# v5_2.net
KiCad netlist of a schematic drawn in EAGLE
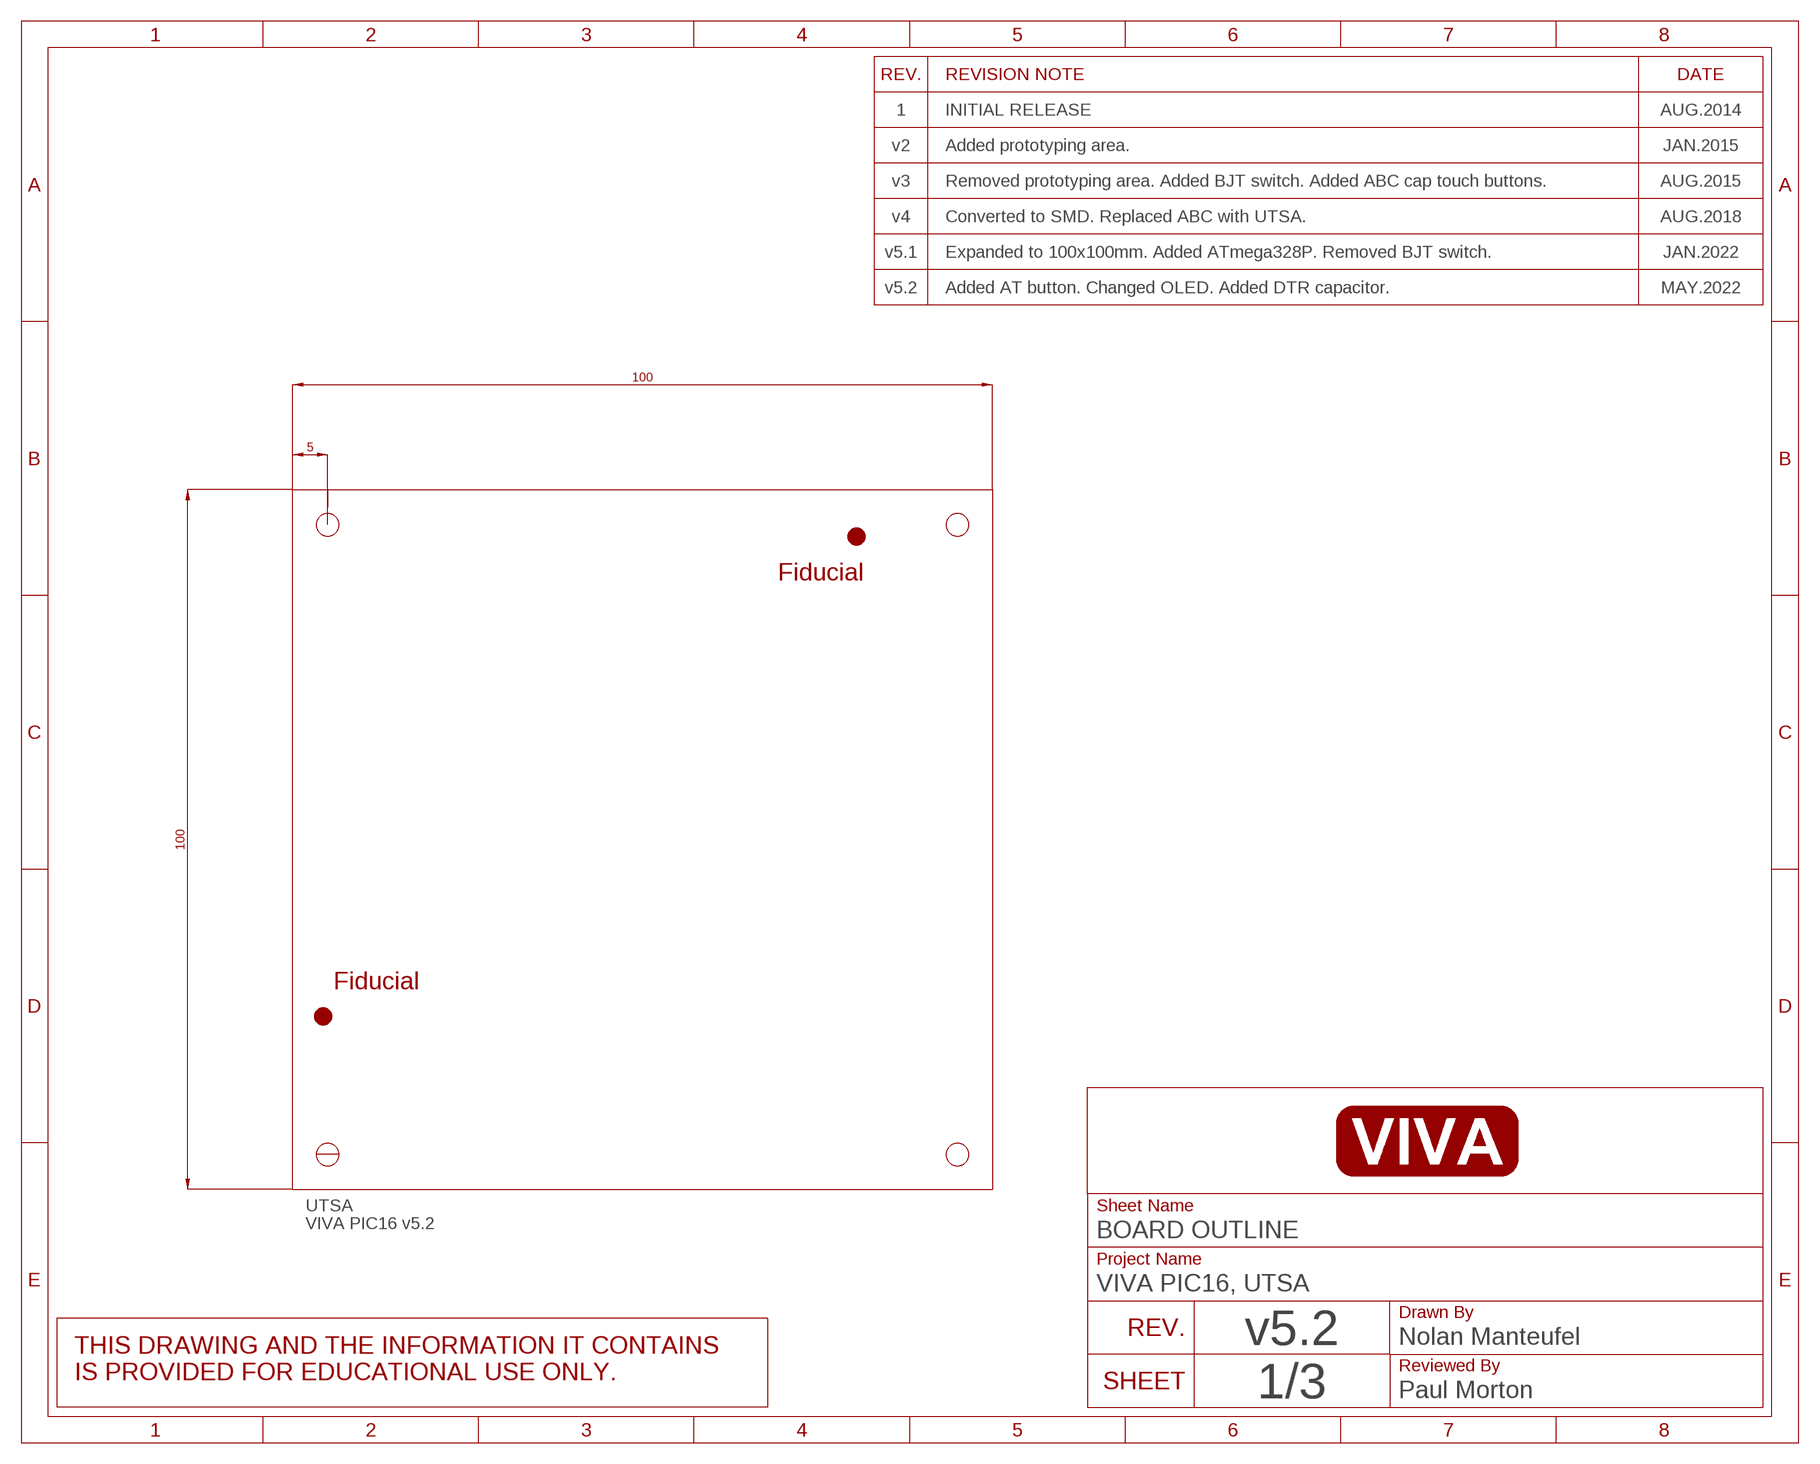
[diagram p0: schematic, sheet 1]
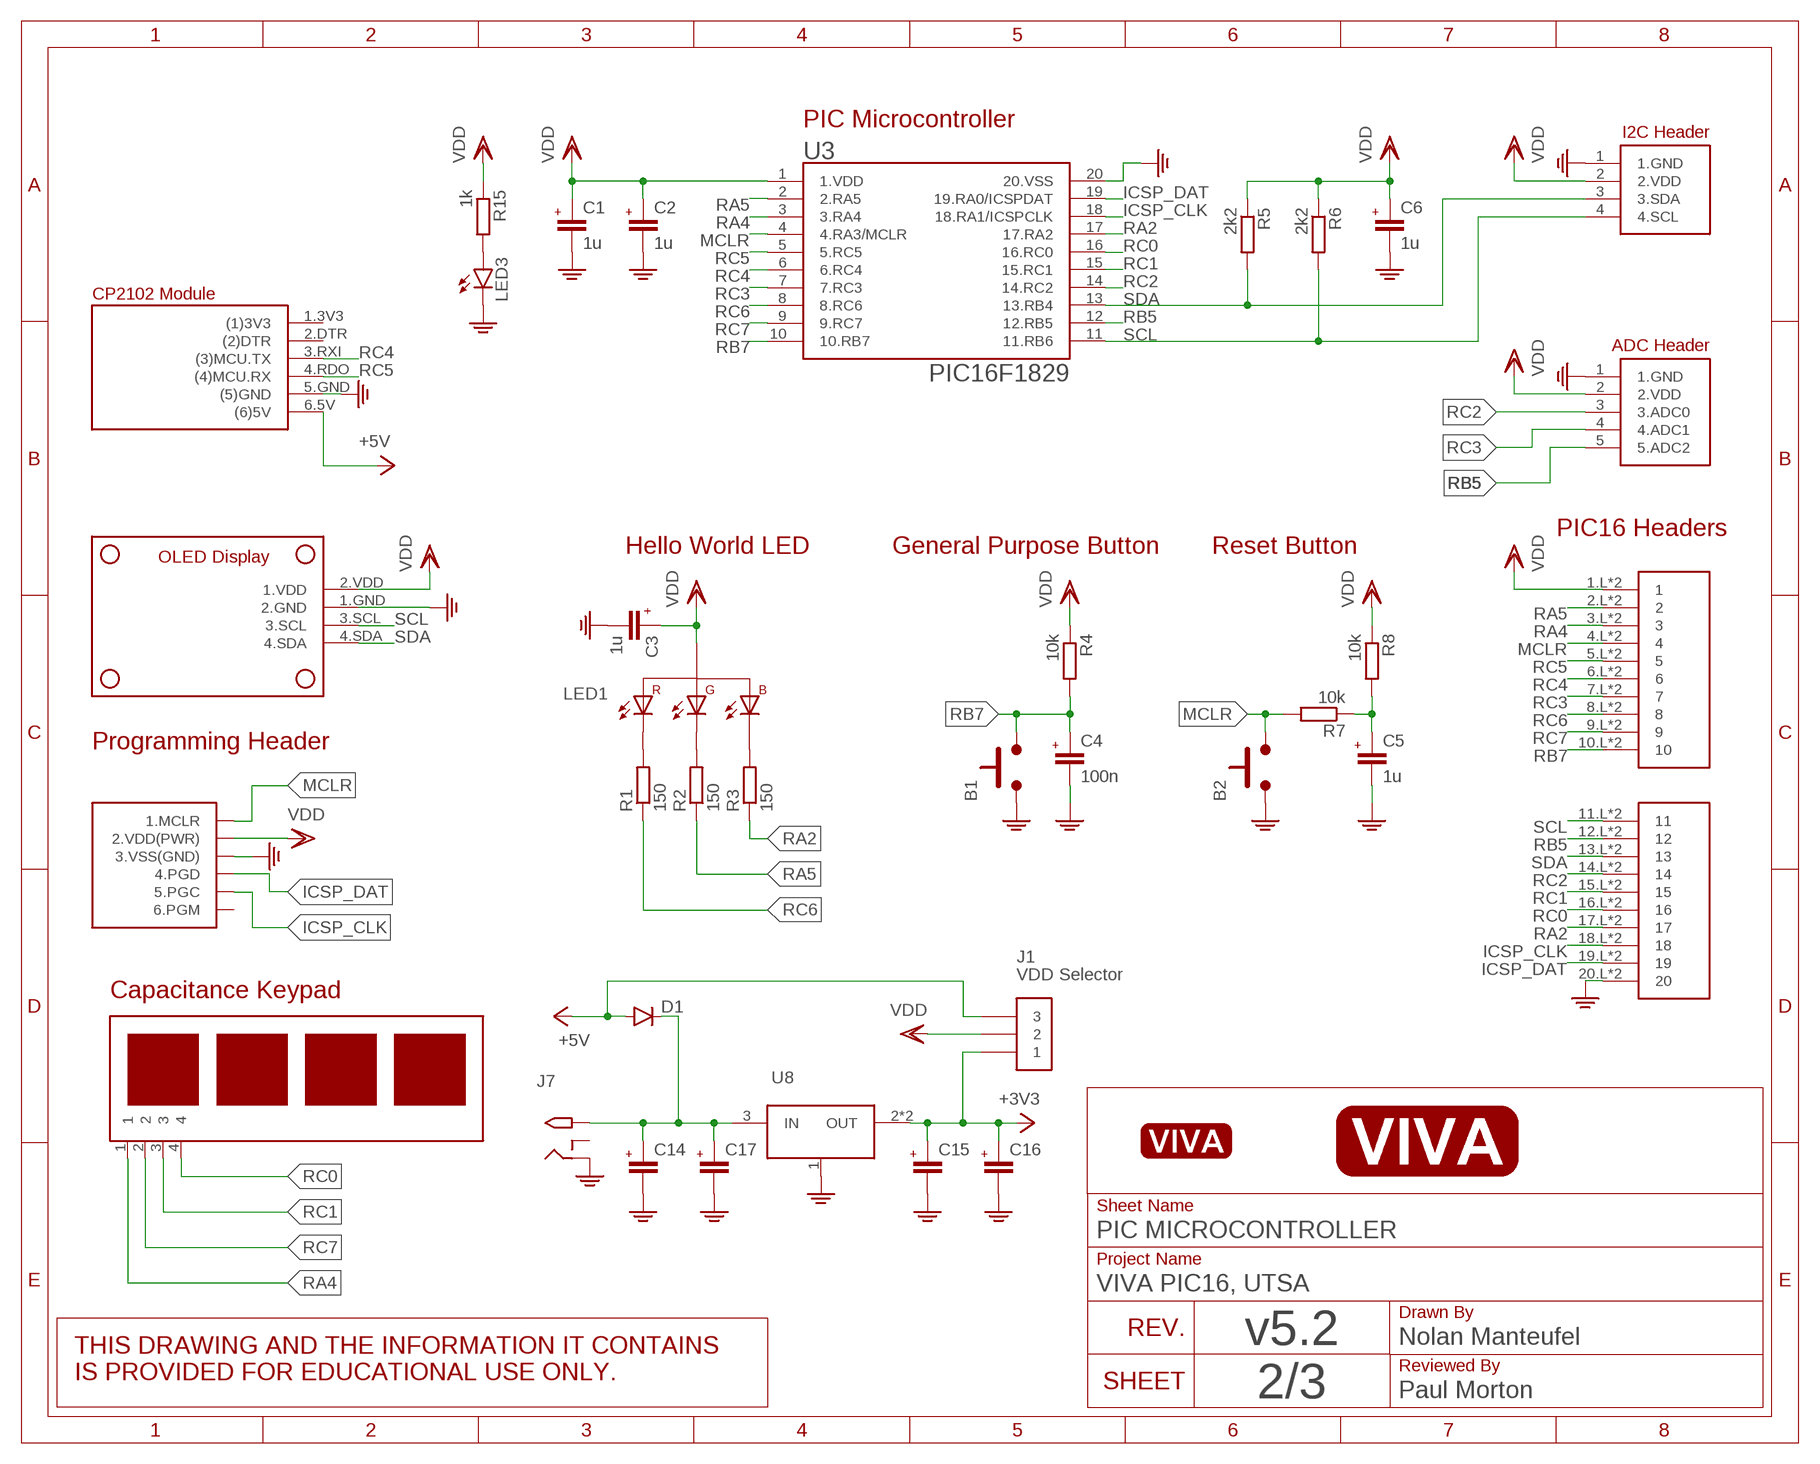
[diagram p1: schematic, sheet 2]
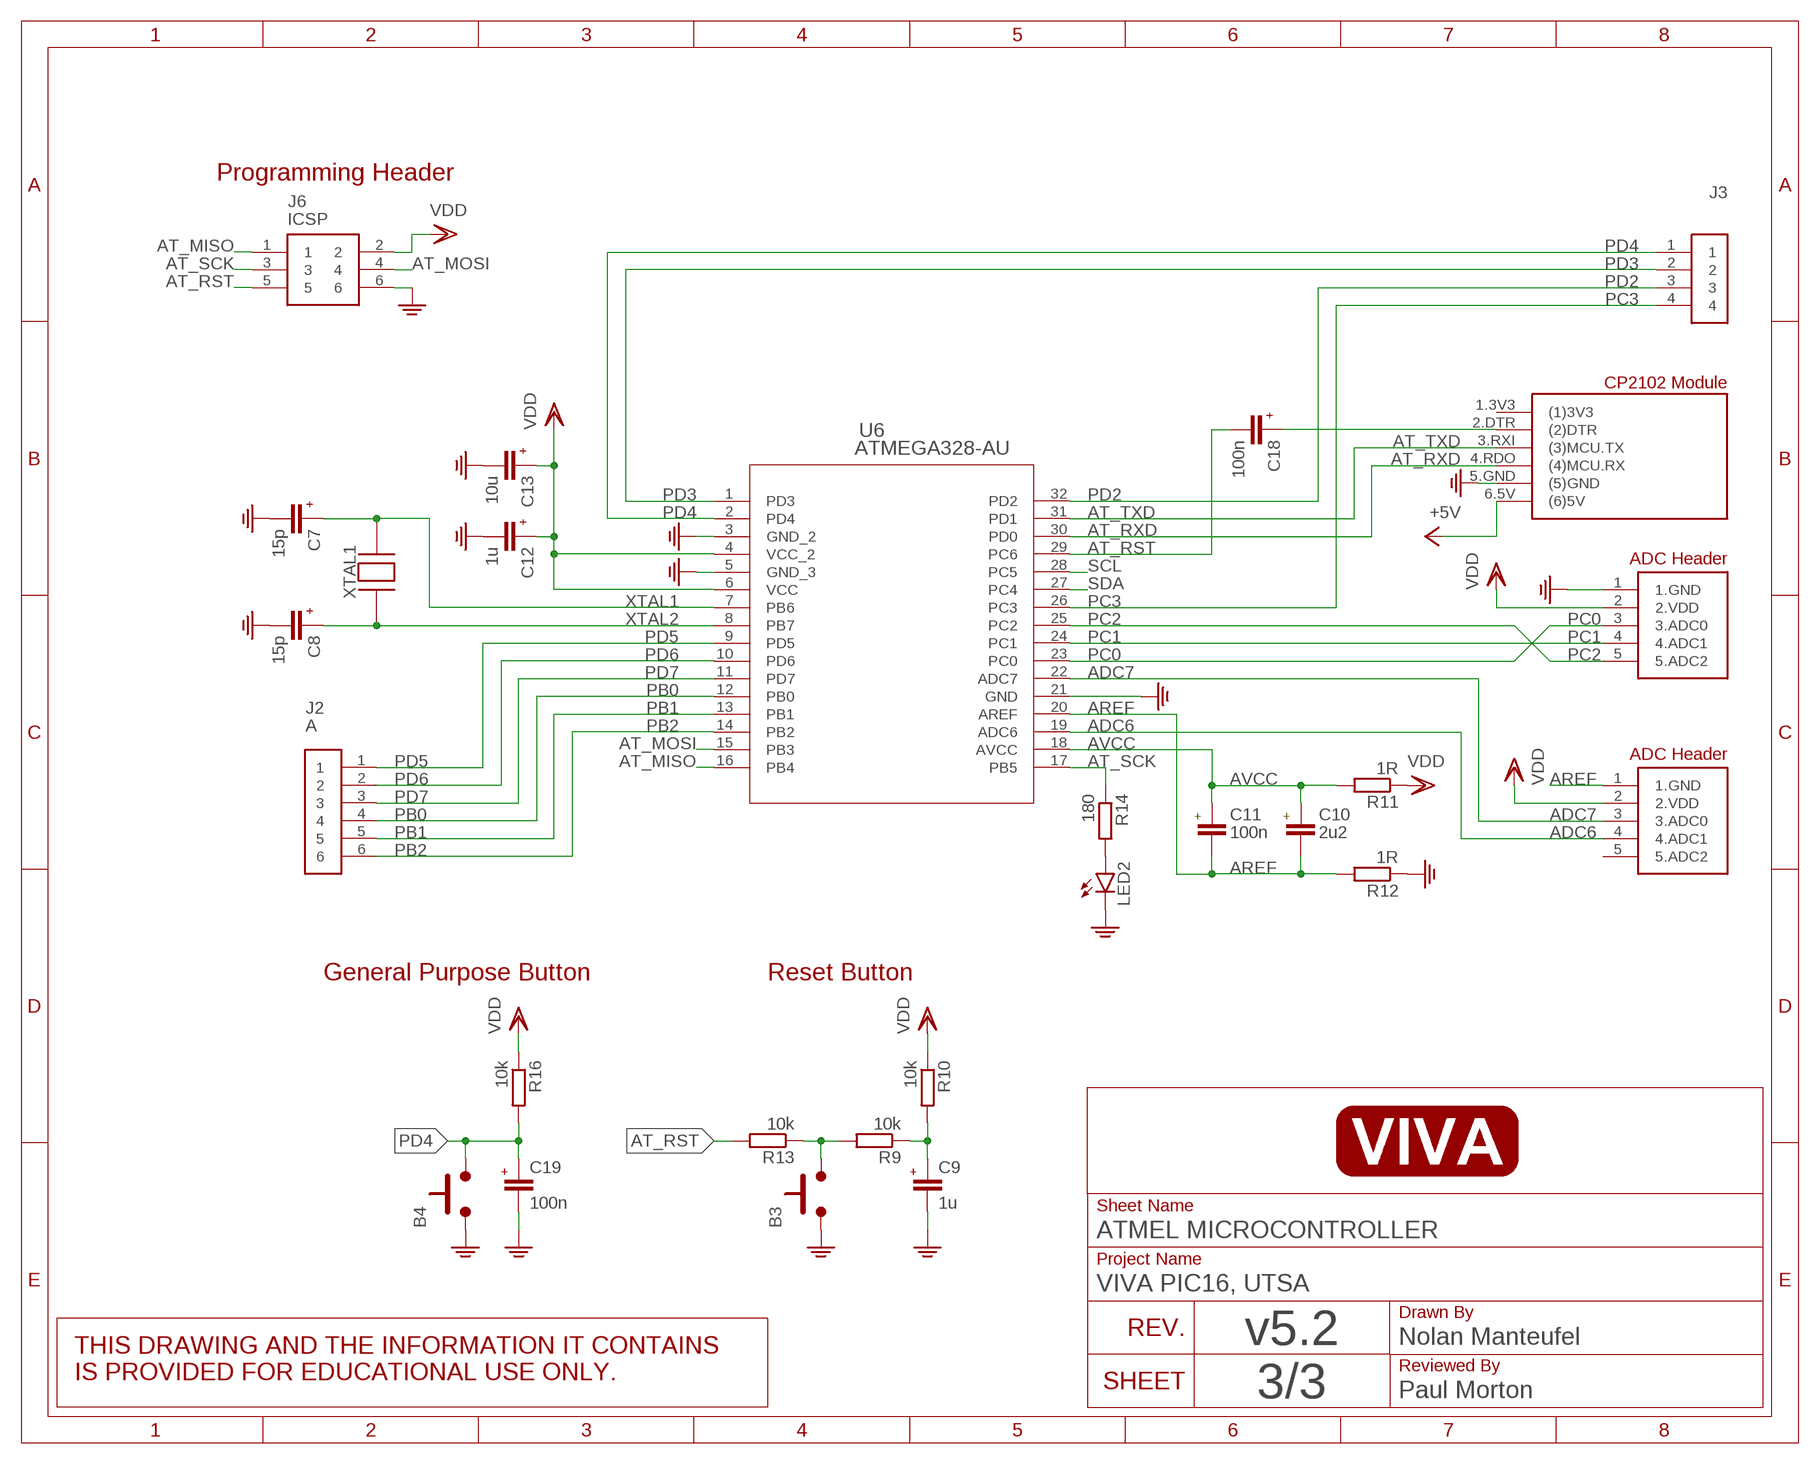
[diagram p2: schematic, sheet 3]

(export (version "E")
  (design (tool "Eeschema 10.0.6"))
  (components
    (comp (ref "A1")
      (value "FIDUCIAL")
      (footprint "eagle-import:FIDUCIAL")
      (libsource (lib "eagle-import") (part "FIDUCIAL"))
    )
    (comp (ref "A2")
      (value "FIDUCIAL")
      (footprint "eagle-import:FIDUCIAL")
      (libsource (lib "eagle-import") (part "FIDUCIAL"))
    )
    (comp (ref "UTSA")
      (value "VIVA PIC16 v5.2")
      (footprint "eagle-import:PCB_100X100")
      (libsource (lib "eagle-import") (part "PCB_100X100"))
    )
    (comp (ref "B3")
      (value "PUSHBUTTON6X6MM")
      (footprint "eagle-import:6X6MM")
      (libsource (lib "eagle-import") (part "PUSHBUTTON6X6MM"))
    )
    (comp (ref "B4")
      (value "PUSHBUTTON6X6MM")
      (footprint "eagle-import:6X6MM")
      (libsource (lib "eagle-import") (part "PUSHBUTTON6X6MM"))
    )
    (comp (ref "C7")
      (value "15p")
      (footprint "eagle-import:C0603")
      (libsource (lib "eagle-import") (part "C0603"))
    )
    (comp (ref "C8")
      (value "15p")
      (footprint "eagle-import:C0603")
      (libsource (lib "eagle-import") (part "C0603"))
    )
    (comp (ref "C9")
      (value "1u")
      (footprint "eagle-import:C0805")
      (libsource (lib "eagle-import") (part "C0805"))
    )
    (comp (ref "C10")
      (value "2u2")
      (footprint "eagle-import:C0805")
      (libsource (lib "eagle-import") (part "C-EU_C0805"))
    )
    (comp (ref "C11")
      (value "100n")
      (footprint "eagle-import:C0805")
      (libsource (lib "eagle-import") (part "C-EU_C0805"))
    )
    (comp (ref "C12")
      (value "1u")
      (footprint "eagle-import:C0805")
      (libsource (lib "eagle-import") (part "C0805"))
    )
    (comp (ref "C13")
      (value "10u")
      (footprint "eagle-import:C0805")
      (libsource (lib "eagle-import") (part "C0805"))
    )
    (comp (ref "C18")
      (value "100n")
      (footprint "eagle-import:C0805")
      (libsource (lib "eagle-import") (part "C0805"))
    )
    (comp (ref "C19")
      (value "100n")
      (footprint "eagle-import:C0805")
      (libsource (lib "eagle-import") (part "C0805"))
    )
    (comp (ref "J2")
      (value "A")
      (footprint "eagle-import:PINS_6")
      (libsource (lib "eagle-import") (part "PINS_6SQUARE"))
    )
    (comp (ref "J3")
      (value "PINS_4_0100")
      (footprint "eagle-import:PINS_4")
      (libsource (lib "eagle-import") (part "PINS_4_0100"))
    )
    (comp (ref "J6")
      (value "ICSP")
      (footprint "eagle-import:PINS_6-2X3")
      (libsource (lib "eagle-import") (part "PINS_6-2X3"))
    )
    (comp (ref "J8")
      (value "VIVA-HEADER-ADC-TEXT")
      (footprint "eagle-import:VIVA-HEADER-ADC")
      (libsource (lib "eagle-import") (part "VIVA-HEADER-ADC-TEXT"))
    )
    (comp (ref "J9")
      (value "VIVA-HEADER-ADC-TEXT")
      (footprint "eagle-import:VIVA-HEADER-ADC")
      (libsource (lib "eagle-import") (part "VIVA-HEADER-ADC-TEXT"))
    )
    (comp (ref "LED2")
      (value "LEDSML0805")
      (footprint "eagle-import:SML0805")
      (libsource (lib "eagle-import") (part "LEDSML0805"))
    )
    (comp (ref "R9")
      (value "10k")
      (footprint "eagle-import:R0805")
      (libsource (lib "eagle-import") (part "R-EU__R0805"))
    )
    (comp (ref "R10")
      (value "10k")
      (footprint "eagle-import:R0805")
      (libsource (lib "eagle-import") (part "R-EU__R0805"))
    )
    (comp (ref "R11")
      (value "1R")
      (footprint "eagle-import:R0805")
      (libsource (lib "eagle-import") (part "R-EU__R0805"))
    )
    (comp (ref "R12")
      (value "1R")
      (footprint "eagle-import:R0805")
      (libsource (lib "eagle-import") (part "R-EU__R0805"))
    )
    (comp (ref "R13")
      (value "10k")
      (footprint "eagle-import:R0805")
      (libsource (lib "eagle-import") (part "R-EU__R0805"))
    )
    (comp (ref "R14")
      (value "180")
      (footprint "eagle-import:R0805")
      (libsource (lib "eagle-import") (part "R-EU__R0805"))
    )
    (comp (ref "R16")
      (value "10k")
      (footprint "eagle-import:R0805")
      (libsource (lib "eagle-import") (part "R-EU__R0805"))
    )
    (comp (ref "U6")
      (value "ATMEGA328-AU")
      (footprint "eagle-import:32A_ATM")
      (fields (field (name "COPYRIGHT") "Copyright (C) 2021 Ultra Librarian. All rights reserved."))
      (libsource (lib "eagle-import") (part "ATMEGA328-AU"))
    )
    (comp (ref "U7")
      (value "VIVA_USB-TTL")
      (footprint "eagle-import:VIVA_USB_TTL_SUBTEXT")
      (libsource (lib "eagle-import") (part "VIVA_USB-TTL"))
    )
    (comp (ref "XTAL1")
      (value "CRYSTAL-SMD")
      (footprint "eagle-import:HC49S-SMD")
      (libsource (lib "eagle-import") (part "CRYSTAL-SMD"))
    )
    (comp (ref "B1")
      (value "PUSHBUTTON6X6MM")
      (footprint "eagle-import:6X6MM")
      (libsource (lib "eagle-import") (part "PUSHBUTTON6X6MM"))
    )
    (comp (ref "B2")
      (value "PUSHBUTTON6X6MM")
      (footprint "eagle-import:6X6MM")
      (libsource (lib "eagle-import") (part "PUSHBUTTON6X6MM"))
    )
    (comp (ref "C1")
      (value "1u")
      (footprint "eagle-import:C0805")
      (libsource (lib "eagle-import") (part "C0805"))
    )
    (comp (ref "C2")
      (value "1u")
      (footprint "eagle-import:C0805")
      (libsource (lib "eagle-import") (part "C0805"))
    )
    (comp (ref "C3")
      (value "1u")
      (footprint "eagle-import:C0805")
      (libsource (lib "eagle-import") (part "C0805"))
    )
    (comp (ref "C4")
      (value "100n")
      (footprint "eagle-import:C0805")
      (libsource (lib "eagle-import") (part "C0805"))
    )
    (comp (ref "C5")
      (value "1u")
      (footprint "eagle-import:C0805")
      (libsource (lib "eagle-import") (part "C0805"))
    )
    (comp (ref "C6")
      (value "1u")
      (footprint "eagle-import:C0805")
      (libsource (lib "eagle-import") (part "C0805"))
    )
    (comp (ref "C14")
      (value "C0805")
      (footprint "eagle-import:C0805")
      (libsource (lib "eagle-import") (part "C0805"))
    )
    (comp (ref "C15")
      (value "C0805")
      (footprint "eagle-import:C0805")
      (libsource (lib "eagle-import") (part "C0805"))
    )
    (comp (ref "C16")
      (value "C0805")
      (footprint "eagle-import:C0805")
      (libsource (lib "eagle-import") (part "C0805"))
    )
    (comp (ref "C17")
      (value "C0805")
      (footprint "eagle-import:C0805")
      (libsource (lib "eagle-import") (part "C0805"))
    )
    (comp (ref "D1")
      (value "DIODE-DO214AC")
      (footprint "eagle-import:DO214AC")
      (libsource (lib "eagle-import") (part "DIODE-DO214AC"))
    )
    (comp (ref "J1")
      (value "VDD Selector")
      (footprint "eagle-import:PINS_3")
      (libsource (lib "eagle-import") (part "PINS_3_2.54"))
    )
    (comp (ref "J4")
      (value "PICKIT3")
      (footprint "eagle-import:PICKIT3")
      (libsource (lib "eagle-import") (part "PICKIT3"))
    )
    (comp (ref "J5")
      (value "VIVA-HEADER-ADC-PIC16")
      (footprint "eagle-import:VIVA-HEADER-ADC-PIC16")
      (libsource (lib "eagle-import") (part "VIVA-HEADER-ADC-PIC16"))
    )
    (comp (ref "J7")
      (value "2.1MMJACKTHM")
      (footprint "eagle-import:PJ-102A")
      (libsource (lib "eagle-import") (part "2.1MMJACKTHM"))
    )
    (comp (ref "LED1")
      (value "LED_RGBLTST-C19FD1WT")
      (footprint "eagle-import:0805_RGB")
      (libsource (lib "eagle-import") (part "LED_RGBLTST-C19FD1WT"))
    )
    (comp (ref "LED3")
      (value "LEDSML0805")
      (footprint "eagle-import:SML0805")
      (libsource (lib "eagle-import") (part "LEDSML0805"))
    )
    (comp (ref "R1")
      (value "150")
      (footprint "eagle-import:R0805")
      (libsource (lib "eagle-import") (part "R-EU__R0805"))
    )
    (comp (ref "R2")
      (value "150")
      (footprint "eagle-import:R0805")
      (libsource (lib "eagle-import") (part "R-EU__R0805"))
    )
    (comp (ref "R3")
      (value "150")
      (footprint "eagle-import:R0805")
      (libsource (lib "eagle-import") (part "R-EU__R0805"))
    )
    (comp (ref "R4")
      (value "10k")
      (footprint "eagle-import:R0805")
      (libsource (lib "eagle-import") (part "R-EU__R0805"))
    )
    (comp (ref "R5")
      (value "2k2")
      (footprint "eagle-import:R0805")
      (libsource (lib "eagle-import") (part "R-EU__R0805"))
    )
    (comp (ref "R6")
      (value "2k2")
      (footprint "eagle-import:R0805")
      (libsource (lib "eagle-import") (part "R-EU__R0805"))
    )
    (comp (ref "R7")
      (value "10k")
      (footprint "eagle-import:R0805")
      (libsource (lib "eagle-import") (part "R-EU__R0805"))
    )
    (comp (ref "R8")
      (value "10k")
      (footprint "eagle-import:R0805")
      (libsource (lib "eagle-import") (part "R-EU__R0805"))
    )
    (comp (ref "R15")
      (value "1k")
      (footprint "eagle-import:R0805")
      (libsource (lib "eagle-import") (part "R-EU__R0805"))
    )
    (comp (ref "U$2")
      (value "VIVA_LOGO")
      (footprint "eagle-import:VIVA_LOGO")
      (libsource (lib "eagle-import") (part "VIVA_LOGO"))
    )
    (comp (ref "U$3")
      (value "VIVA_OLEDGND")
      (footprint "eagle-import:VIVA_OLED-I2C-ALT")
      (libsource (lib "eagle-import") (part "VIVA_OLEDGND"))
    )
    (comp (ref "U1")
      (value "VIVA_UTSA-KEYPADV5")
      (footprint "eagle-import:VIVA_UTSA-KEYPAD-V5")
      (libsource (lib "eagle-import") (part "VIVA_UTSA-KEYPADV5"))
    )
    (comp (ref "U2")
      (value "VIVA_USB-TTL")
      (footprint "eagle-import:VIVA_USB_TTL_SUBTEXT")
      (libsource (lib "eagle-import") (part "VIVA_USB-TTL"))
    )
    (comp (ref "U3")
      (value "PIC16F1829")
      (footprint "eagle-import:SOP20-NEW")
      (libsource (lib "eagle-import") (part "PIC16F1829300"))
    )
    (comp (ref "U4")
      (value "VIVA-HEADER-I2C-RA")
      (footprint "eagle-import:VIVA-HEADER-I2C-RA")
      (libsource (lib "eagle-import") (part "VIVA-HEADER-I2C-RA"))
    )
    (comp (ref "U5")
      (value "VIVA_PIC16BOARD")
      (footprint "eagle-import:VIVA_PIC16")
      (libsource (lib "eagle-import") (part "VIVA_PIC16BOARD"))
    )
    (comp (ref "U8")
      (value "REGULATOR_SCHLM1117")
      (footprint "eagle-import:SOT223")
      (libsource (lib "eagle-import") (part "REGULATOR_SCHLM1117"))
    )
  )
  (nets
    (net (code "1") (name "+3V3") (class "Default")
      (node (ref "C15") (pin "1") (pinfunction "+_1") (pintype "passive"))
      (node (ref "C16") (pin "1") (pinfunction "+_1") (pintype "passive"))
      (node (ref "J1") (pin "1") (pinfunction "1_1") (pintype "bidirectional"))
      (node (ref "U8") (pin "2") (pinfunction "OUT_2") (pintype "bidirectional"))
      (node (ref "U8") (pin "4.TAB") (pinfunction "OUT_4.TAB") (pintype "bidirectional"))
    )
    (net (code "2") (name "+5V") (class "Default")
      (node (ref "D1") (pin "A") (pinfunction "A_A") (pintype "passive"))
      (node (ref "J1") (pin "3") (pinfunction "3_3") (pintype "bidirectional"))
      (node (ref "U2") (pin "6.5V") (pinfunction "(6)5V_6.5V") (pintype "bidirectional"))
      (node (ref "U7") (pin "6.5V") (pinfunction "(6)5V_6.5V") (pintype "bidirectional"))
    )
    (net (code "3") (name "ADC6") (class "Default")
      (node (ref "J8") (pin "4") (pinfunction "4.ADC1_4") (pintype "bidirectional"))
      (node (ref "U6") (pin "19") (pinfunction "ADC6_19") (pintype "passive"))
    )
    (net (code "4") (name "ADC7") (class "Default")
      (node (ref "J8") (pin "3") (pinfunction "3.ADC0_3") (pintype "bidirectional"))
      (node (ref "U6") (pin "22") (pinfunction "ADC7_22") (pintype "passive"))
    )
    (net (code "5") (name "AREF") (class "Default")
      (node (ref "C10") (pin "2") (pinfunction "2_2") (pintype "passive"))
      (node (ref "C11") (pin "2") (pinfunction "2_2") (pintype "passive"))
      (node (ref "J8") (pin "1") (pinfunction "1.GND_1") (pintype "bidirectional"))
      (node (ref "R12") (pin "2") (pinfunction "2_2") (pintype "passive"))
      (node (ref "U6") (pin "20") (pinfunction "AREF_20") (pintype "passive"))
    )
    (net (code "6") (name "AT_MISO") (class "Default")
      (node (ref "J6") (pin "1") (pinfunction "1_1") (pintype "bidirectional"))
      (node (ref "U6") (pin "16") (pinfunction "PB4_16") (pintype "bidirectional"))
    )
    (net (code "7") (name "AT_MOSI") (class "Default")
      (node (ref "J6") (pin "4") (pinfunction "4_4") (pintype "bidirectional"))
      (node (ref "U6") (pin "15") (pinfunction "PB3_15") (pintype "bidirectional"))
    )
    (net (code "8") (name "AT_RST") (class "Default")
      (node (ref "C18") (pin "2") (pinfunction "-_2") (pintype "passive"))
      (node (ref "J6") (pin "5") (pinfunction "5_5") (pintype "bidirectional"))
      (node (ref "R13") (pin "2") (pinfunction "2_2") (pintype "passive"))
      (node (ref "U6") (pin "29") (pinfunction "PC6_29") (pintype "bidirectional"))
    )
    (net (code "9") (name "AT_RXD") (class "Default")
      (node (ref "U6") (pin "30") (pinfunction "PD0_30") (pintype "bidirectional"))
      (node (ref "U7") (pin "4.RDO") (pinfunction "(4)MCU.RX_4.RDO") (pintype "bidirectional"))
    )
    (net (code "10") (name "AT_SCK") (class "Default")
      (node (ref "J6") (pin "3") (pinfunction "3_3") (pintype "bidirectional"))
      (node (ref "R14") (pin "1") (pinfunction "1_1") (pintype "passive"))
      (node (ref "U6") (pin "17") (pinfunction "PB5_17") (pintype "bidirectional"))
    )
    (net (code "11") (name "AT_TXD") (class "Default")
      (node (ref "U6") (pin "31") (pinfunction "PD1_31") (pintype "bidirectional"))
      (node (ref "U7") (pin "3.RXI") (pinfunction "(3)MCU.TX_3.RXI") (pintype "bidirectional"))
    )
    (net (code "12") (name "AVCC") (class "Default")
      (node (ref "C10") (pin "1") (pinfunction "1_1") (pintype "passive"))
      (node (ref "C11") (pin "1") (pinfunction "1_1") (pintype "passive"))
      (node (ref "R11") (pin "2") (pinfunction "2_2") (pintype "passive"))
      (node (ref "U6") (pin "18") (pinfunction "AVCC_18") (pintype "power_in"))
    )
    (net (code "13") (name "GND") (class "Default")
      (node (ref "B1") (pin "1.A") (pinfunction "1_1.A") (pintype "bidirectional"))
      (node (ref "B1") (pin "2.A") (pinfunction "1_2.A") (pintype "bidirectional"))
      (node (ref "B2") (pin "1.A") (pinfunction "1_1.A") (pintype "bidirectional"))
      (node (ref "B2") (pin "2.A") (pinfunction "1_2.A") (pintype "bidirectional"))
      (node (ref "B3") (pin "1.A") (pinfunction "1_1.A") (pintype "bidirectional"))
      (node (ref "B3") (pin "2.A") (pinfunction "1_2.A") (pintype "bidirectional"))
      (node (ref "B4") (pin "1.A") (pinfunction "1_1.A") (pintype "bidirectional"))
      (node (ref "B4") (pin "2.A") (pinfunction "1_2.A") (pintype "bidirectional"))
      (node (ref "C1") (pin "2") (pinfunction "-_2") (pintype "passive"))
      (node (ref "C12") (pin "2") (pinfunction "-_2") (pintype "passive"))
      (node (ref "C13") (pin "2") (pinfunction "-_2") (pintype "passive"))
      (node (ref "C14") (pin "2") (pinfunction "-_2") (pintype "passive"))
      (node (ref "C15") (pin "2") (pinfunction "-_2") (pintype "passive"))
      (node (ref "C16") (pin "2") (pinfunction "-_2") (pintype "passive"))
      (node (ref "C17") (pin "2") (pinfunction "-_2") (pintype "passive"))
      (node (ref "C19") (pin "2") (pinfunction "-_2") (pintype "passive"))
      (node (ref "C2") (pin "2") (pinfunction "-_2") (pintype "passive"))
      (node (ref "C3") (pin "2") (pinfunction "-_2") (pintype "passive"))
      (node (ref "C4") (pin "2") (pinfunction "-_2") (pintype "passive"))
      (node (ref "C5") (pin "2") (pinfunction "-_2") (pintype "passive"))
      (node (ref "C6") (pin "2") (pinfunction "-_2") (pintype "passive"))
      (node (ref "C7") (pin "1") (pinfunction "-_1") (pintype "passive"))
      (node (ref "C8") (pin "1") (pinfunction "-_1") (pintype "passive"))
      (node (ref "C9") (pin "2") (pinfunction "-_2") (pintype "passive"))
      (node (ref "J4") (pin "3") (pinfunction "3.VSS(GND)_3") (pintype "bidirectional"))
      (node (ref "J5") (pin "1") (pinfunction "1.GND_1") (pintype "bidirectional"))
      (node (ref "J6") (pin "6") (pinfunction "6_6") (pintype "bidirectional"))
      (node (ref "J7") (pin "RING") (pinfunction "RING_RING") (pintype "bidirectional"))
      (node (ref "J9") (pin "1") (pinfunction "1.GND_1") (pintype "bidirectional"))
      (node (ref "LED2") (pin "C") (pinfunction "C_C") (pintype "passive"))
      (node (ref "LED3") (pin "C") (pinfunction "C_C") (pintype "passive"))
      (node (ref "R12") (pin "1") (pinfunction "1_1") (pintype "passive"))
      (node (ref "U$3") (pin "1.GND") (pinfunction "2.GND_1.GND") (pintype "bidirectional"))
      (node (ref "U2") (pin "5.GND") (pinfunction "(5)GND_5.GND") (pintype "bidirectional"))
      (node (ref "U3") (pin "20") (pinfunction "20.VSS_20") (pintype "bidirectional"))
      (node (ref "U4") (pin "1") (pinfunction "1.GND_1") (pintype "bidirectional"))
      (node (ref "U5") (pin "20.L") (pinfunction "20_20.L") (pintype "bidirectional"))
      (node (ref "U5") (pin "20.R") (pinfunction "20_20.R") (pintype "bidirectional"))
      (node (ref "U6") (pin "21") (pinfunction "GND_21") (pintype "power_in"))
      (node (ref "U6") (pin "3") (pinfunction "GND_2_3") (pintype "power_in"))
      (node (ref "U6") (pin "5") (pinfunction "GND_3_5") (pintype "power_in"))
      (node (ref "U7") (pin "5.GND") (pinfunction "(5)GND_5.GND") (pintype "bidirectional"))
      (node (ref "U8") (pin "1") (pinfunction "GND_1") (pintype "bidirectional"))
    )
    (net (code "14") (name "ICSP_CLK") (class "Default")
      (node (ref "J4") (pin "5") (pinfunction "5.PGC_5") (pintype "bidirectional"))
      (node (ref "U3") (pin "18") (pinfunction "18.RA1/ICSPCLK_18") (pintype "bidirectional"))
      (node (ref "U5") (pin "18.L") (pinfunction "18_18.L") (pintype "bidirectional"))
      (node (ref "U5") (pin "18.R") (pinfunction "18_18.R") (pintype "bidirectional"))
    )
    (net (code "15") (name "ICSP_DAT") (class "Default")
      (node (ref "J4") (pin "4") (pinfunction "4.PGD_4") (pintype "bidirectional"))
      (node (ref "U3") (pin "19") (pinfunction "19.RA0/ICSPDAT_19") (pintype "bidirectional"))
      (node (ref "U5") (pin "19.L") (pinfunction "19_19.L") (pintype "bidirectional"))
      (node (ref "U5") (pin "19.R") (pinfunction "19_19.R") (pintype "bidirectional"))
    )
    (net (code "16") (name "MCLR") (class "Default")
      (node (ref "B2") (pin "3.B") (pinfunction "2_3.B") (pintype "bidirectional"))
      (node (ref "B2") (pin "4.B") (pinfunction "2_4.B") (pintype "bidirectional"))
      (node (ref "J4") (pin "1") (pinfunction "1.MCLR_1") (pintype "bidirectional"))
      (node (ref "R7") (pin "2") (pinfunction "2_2") (pintype "passive"))
      (node (ref "U3") (pin "4") (pinfunction "4.RA3/MCLR_4") (pintype "bidirectional"))
      (node (ref "U5") (pin "4.L") (pinfunction "4_4.L") (pintype "bidirectional"))
      (node (ref "U5") (pin "4.R") (pinfunction "4_4.R") (pintype "bidirectional"))
    )
    (net (code "17") (name "Net-(B3-2-Pad3.B)") (class "Default")
      (node (ref "B3") (pin "3.B") (pinfunction "2_3.B") (pintype "bidirectional"))
      (node (ref "B3") (pin "4.B") (pinfunction "2_4.B") (pintype "bidirectional"))
      (node (ref "R13") (pin "1") (pinfunction "1_1") (pintype "passive"))
      (node (ref "R9") (pin "2") (pinfunction "2_2") (pintype "passive"))
    )
    (net (code "18") (name "Net-(C5-+)") (class "Default")
      (node (ref "C5") (pin "1") (pinfunction "+_1") (pintype "passive"))
      (node (ref "R7") (pin "1") (pinfunction "1_1") (pintype "passive"))
      (node (ref "R8") (pin "2") (pinfunction "2_2") (pintype "passive"))
    )
    (net (code "19") (name "Net-(C9-+)") (class "Default")
      (node (ref "C9") (pin "1") (pinfunction "+_1") (pintype "passive"))
      (node (ref "R10") (pin "2") (pinfunction "2_2") (pintype "passive"))
      (node (ref "R9") (pin "1") (pinfunction "1_1") (pintype "passive"))
    )
    (net (code "20") (name "Net-(C14-+)") (class "Default")
      (node (ref "C14") (pin "1") (pinfunction "+_1") (pintype "passive"))
      (node (ref "C17") (pin "1") (pinfunction "+_1") (pintype "passive"))
      (node (ref "D1") (pin "C") (pinfunction "C_C") (pintype "passive"))
      (node (ref "J7") (pin "TIP") (pinfunction "TIP_TIP") (pintype "bidirectional"))
      (node (ref "U8") (pin "3") (pinfunction "IN_3") (pintype "bidirectional"))
    )
    (net (code "21") (name "Net-(C18-+)") (class "Default")
      (node (ref "C18") (pin "1") (pinfunction "+_1") (pintype "passive"))
      (node (ref "U7") (pin "2.DTR") (pinfunction "(2)DTR_2.DTR") (pintype "bidirectional"))
    )
    (net (code "22") (name "Net-(LED1-1.R-)") (class "Default")
      (node (ref "LED1") (pin "2") (pinfunction "1.R-_2") (pintype "passive"))
      (node (ref "R1") (pin "2") (pinfunction "2_2") (pintype "passive"))
    )
    (net (code "23") (name "Net-(LED1-2.G-)") (class "Default")
      (node (ref "LED1") (pin "3") (pinfunction "2.G-_3") (pintype "passive"))
      (node (ref "R2") (pin "2") (pinfunction "2_2") (pintype "passive"))
    )
    (net (code "24") (name "Net-(LED1-4.B-)") (class "Default")
      (node (ref "LED1") (pin "1") (pinfunction "4.B-_1") (pintype "passive"))
      (node (ref "R3") (pin "2") (pinfunction "2_2") (pintype "passive"))
    )
    (net (code "25") (name "Net-(LED2-PadA)") (class "Default")
      (node (ref "LED2") (pin "A") (pinfunction "A_A") (pintype "passive"))
      (node (ref "R14") (pin "2") (pinfunction "2_2") (pintype "passive"))
    )
    (net (code "26") (name "Net-(LED3-PadA)") (class "Default")
      (node (ref "LED3") (pin "A") (pinfunction "A_A") (pintype "passive"))
      (node (ref "R15") (pin "2") (pinfunction "2_2") (pintype "passive"))
    )
    (net (code "27") (name "PB0") (class "Default")
      (node (ref "J2") (pin "4") (pinfunction "4_4") (pintype "bidirectional"))
      (node (ref "U6") (pin "12") (pinfunction "PB0_12") (pintype "bidirectional"))
    )
    (net (code "28") (name "PB1") (class "Default")
      (node (ref "J2") (pin "5") (pinfunction "5_5") (pintype "bidirectional"))
      (node (ref "U6") (pin "13") (pinfunction "PB1_13") (pintype "bidirectional"))
    )
    (net (code "29") (name "PB2") (class "Default")
      (node (ref "J2") (pin "6") (pinfunction "6_6") (pintype "bidirectional"))
      (node (ref "U6") (pin "14") (pinfunction "PB2_14") (pintype "bidirectional"))
    )
    (net (code "30") (name "PC0") (class "Default")
      (node (ref "J9") (pin "3") (pinfunction "3.ADC0_3") (pintype "bidirectional"))
      (node (ref "U6") (pin "23") (pinfunction "PC0_23") (pintype "bidirectional"))
    )
    (net (code "31") (name "PC1") (class "Default")
      (node (ref "J9") (pin "4") (pinfunction "4.ADC1_4") (pintype "bidirectional"))
      (node (ref "U6") (pin "24") (pinfunction "PC1_24") (pintype "bidirectional"))
    )
    (net (code "32") (name "PC2") (class "Default")
      (node (ref "J9") (pin "5") (pinfunction "5.ADC2_5") (pintype "bidirectional"))
      (node (ref "U6") (pin "25") (pinfunction "PC2_25") (pintype "bidirectional"))
    )
    (net (code "33") (name "PC3") (class "Default")
      (node (ref "J3") (pin "4") (pinfunction "4_4") (pintype "bidirectional"))
      (node (ref "U6") (pin "26") (pinfunction "PC3_26") (pintype "bidirectional"))
    )
    (net (code "34") (name "PD2") (class "Default")
      (node (ref "J3") (pin "3") (pinfunction "3_3") (pintype "bidirectional"))
      (node (ref "U6") (pin "32") (pinfunction "PD2_32") (pintype "bidirectional"))
    )
    (net (code "35") (name "PD3") (class "Default")
      (node (ref "J3") (pin "2") (pinfunction "2_2") (pintype "bidirectional"))
      (node (ref "U6") (pin "1") (pinfunction "PD3_1") (pintype "bidirectional"))
    )
    (net (code "36") (name "PD4") (class "Default")
      (node (ref "B4") (pin "3.B") (pinfunction "2_3.B") (pintype "bidirectional"))
      (node (ref "B4") (pin "4.B") (pinfunction "2_4.B") (pintype "bidirectional"))
      (node (ref "C19") (pin "1") (pinfunction "+_1") (pintype "passive"))
      (node (ref "J3") (pin "1") (pinfunction "1_1") (pintype "bidirectional"))
      (node (ref "R16") (pin "2") (pinfunction "2_2") (pintype "passive"))
      (node (ref "U6") (pin "2") (pinfunction "PD4_2") (pintype "bidirectional"))
    )
    (net (code "37") (name "PD5") (class "Default")
      (node (ref "J2") (pin "1") (pinfunction "1_1") (pintype "bidirectional"))
      (node (ref "U6") (pin "9") (pinfunction "PD5_9") (pintype "bidirectional"))
    )
    (net (code "38") (name "PD6") (class "Default")
      (node (ref "J2") (pin "2") (pinfunction "2_2") (pintype "bidirectional"))
      (node (ref "U6") (pin "10") (pinfunction "PD6_10") (pintype "bidirectional"))
    )
    (net (code "39") (name "PD7") (class "Default")
      (node (ref "J2") (pin "3") (pinfunction "3_3") (pintype "bidirectional"))
      (node (ref "U6") (pin "11") (pinfunction "PD7_11") (pintype "bidirectional"))
    )
    (net (code "40") (name "RA2") (class "Default")
      (node (ref "R3") (pin "1") (pinfunction "1_1") (pintype "passive"))
      (node (ref "U3") (pin "17") (pinfunction "17.RA2_17") (pintype "bidirectional"))
      (node (ref "U5") (pin "17.L") (pinfunction "17_17.L") (pintype "bidirectional"))
      (node (ref "U5") (pin "17.R") (pinfunction "17_17.R") (pintype "bidirectional"))
    )
    (net (code "41") (name "RA4") (class "Default")
      (node (ref "U1") (pin "1") (pinfunction "1_1") (pintype "bidirectional"))
      (node (ref "U3") (pin "3") (pinfunction "3.RA4_3") (pintype "bidirectional"))
      (node (ref "U5") (pin "3.L") (pinfunction "3_3.L") (pintype "bidirectional"))
      (node (ref "U5") (pin "3.R") (pinfunction "3_3.R") (pintype "bidirectional"))
    )
    (net (code "42") (name "RA5") (class "Default")
      (node (ref "R2") (pin "1") (pinfunction "1_1") (pintype "passive"))
      (node (ref "U3") (pin "2") (pinfunction "2.RA5_2") (pintype "bidirectional"))
      (node (ref "U5") (pin "2.L") (pinfunction "2_2.L") (pintype "bidirectional"))
      (node (ref "U5") (pin "2.R") (pinfunction "2_2.R") (pintype "bidirectional"))
    )
    (net (code "43") (name "RB5") (class "Default")
      (node (ref "J5") (pin "5") (pinfunction "5.ADC2_5") (pintype "bidirectional"))
      (node (ref "U3") (pin "12") (pinfunction "12.RB5_12") (pintype "bidirectional"))
      (node (ref "U5") (pin "12.L") (pinfunction "12_12.L") (pintype "bidirectional"))
      (node (ref "U5") (pin "12.R") (pinfunction "12_12.R") (pintype "bidirectional"))
    )
    (net (code "44") (name "RB7") (class "Default")
      (node (ref "B1") (pin "3.B") (pinfunction "2_3.B") (pintype "bidirectional"))
      (node (ref "B1") (pin "4.B") (pinfunction "2_4.B") (pintype "bidirectional"))
      (node (ref "C4") (pin "1") (pinfunction "+_1") (pintype "passive"))
      (node (ref "R4") (pin "2") (pinfunction "2_2") (pintype "passive"))
      (node (ref "U3") (pin "10") (pinfunction "10.RB7_10") (pintype "bidirectional"))
      (node (ref "U5") (pin "10.L") (pinfunction "10_10.L") (pintype "bidirectional"))
      (node (ref "U5") (pin "10.R") (pinfunction "10_10.R") (pintype "bidirectional"))
    )
    (net (code "45") (name "RC0") (class "Default")
      (node (ref "U1") (pin "4") (pinfunction "4_4") (pintype "bidirectional"))
      (node (ref "U3") (pin "16") (pinfunction "16.RC0_16") (pintype "bidirectional"))
      (node (ref "U5") (pin "16.L") (pinfunction "16_16.L") (pintype "bidirectional"))
      (node (ref "U5") (pin "16.R") (pinfunction "16_16.R") (pintype "bidirectional"))
    )
    (net (code "46") (name "RC1") (class "Default")
      (node (ref "U1") (pin "3") (pinfunction "3_3") (pintype "bidirectional"))
      (node (ref "U3") (pin "15") (pinfunction "15.RC1_15") (pintype "bidirectional"))
      (node (ref "U5") (pin "15.L") (pinfunction "15_15.L") (pintype "bidirectional"))
      (node (ref "U5") (pin "15.R") (pinfunction "15_15.R") (pintype "bidirectional"))
    )
    (net (code "47") (name "RC2") (class "Default")
      (node (ref "J5") (pin "3") (pinfunction "3.ADC0_3") (pintype "bidirectional"))
      (node (ref "U3") (pin "14") (pinfunction "14.RC2_14") (pintype "bidirectional"))
      (node (ref "U5") (pin "14.L") (pinfunction "14_14.L") (pintype "bidirectional"))
      (node (ref "U5") (pin "14.R") (pinfunction "14_14.R") (pintype "bidirectional"))
    )
    (net (code "48") (name "RC3") (class "Default")
      (node (ref "J5") (pin "4") (pinfunction "4.ADC1_4") (pintype "bidirectional"))
      (node (ref "U3") (pin "7") (pinfunction "7.RC3_7") (pintype "bidirectional"))
      (node (ref "U5") (pin "7.L") (pinfunction "7_7.L") (pintype "bidirectional"))
      (node (ref "U5") (pin "7.R") (pinfunction "7_7.R") (pintype "bidirectional"))
    )
    (net (code "49") (name "RC4") (class "Default")
      (node (ref "U2") (pin "3.RXI") (pinfunction "(3)MCU.TX_3.RXI") (pintype "bidirectional"))
      (node (ref "U3") (pin "6") (pinfunction "6.RC4_6") (pintype "bidirectional"))
      (node (ref "U5") (pin "6.L") (pinfunction "6_6.L") (pintype "bidirectional"))
      (node (ref "U5") (pin "6.R") (pinfunction "6_6.R") (pintype "bidirectional"))
    )
    (net (code "50") (name "RC5") (class "Default")
      (node (ref "U2") (pin "4.RDO") (pinfunction "(4)MCU.RX_4.RDO") (pintype "bidirectional"))
      (node (ref "U3") (pin "5") (pinfunction "5.RC5_5") (pintype "bidirectional"))
      (node (ref "U5") (pin "5.L") (pinfunction "5_5.L") (pintype "bidirectional"))
      (node (ref "U5") (pin "5.R") (pinfunction "5_5.R") (pintype "bidirectional"))
    )
    (net (code "51") (name "RC6") (class "Default")
      (node (ref "R1") (pin "1") (pinfunction "1_1") (pintype "passive"))
      (node (ref "U3") (pin "8") (pinfunction "8.RC6_8") (pintype "bidirectional"))
      (node (ref "U5") (pin "8.L") (pinfunction "8_8.L") (pintype "bidirectional"))
      (node (ref "U5") (pin "8.R") (pinfunction "8_8.R") (pintype "bidirectional"))
    )
    (net (code "52") (name "RC7") (class "Default")
      (node (ref "U1") (pin "2") (pinfunction "2_2") (pintype "bidirectional"))
      (node (ref "U3") (pin "9") (pinfunction "9.RC7_9") (pintype "bidirectional"))
      (node (ref "U5") (pin "9.L") (pinfunction "9_9.L") (pintype "bidirectional"))
      (node (ref "U5") (pin "9.R") (pinfunction "9_9.R") (pintype "bidirectional"))
    )
    (net (code "53") (name "SCL") (class "Default")
      (node (ref "R6") (pin "2") (pinfunction "2_2") (pintype "passive"))
      (node (ref "U$3") (pin "3.SCL") (pinfunction "3.SCL_3.SCL") (pintype "bidirectional"))
      (node (ref "U3") (pin "11") (pinfunction "11.RB6_11") (pintype "bidirectional"))
      (node (ref "U4") (pin "4") (pinfunction "4.SCL_4") (pintype "bidirectional"))
      (node (ref "U5") (pin "11.L") (pinfunction "11_11.L") (pintype "bidirectional"))
      (node (ref "U5") (pin "11.R") (pinfunction "11_11.R") (pintype "bidirectional"))
      (node (ref "U6") (pin "28") (pinfunction "PC5_28") (pintype "bidirectional"))
    )
    (net (code "54") (name "SDA") (class "Default")
      (node (ref "R5") (pin "2") (pinfunction "2_2") (pintype "passive"))
      (node (ref "U$3") (pin "4.SDA") (pinfunction "4.SDA_4.SDA") (pintype "bidirectional"))
      (node (ref "U3") (pin "13") (pinfunction "13.RB4_13") (pintype "bidirectional"))
      (node (ref "U4") (pin "3") (pinfunction "3.SDA_3") (pintype "bidirectional"))
      (node (ref "U5") (pin "13.L") (pinfunction "13_13.L") (pintype "bidirectional"))
      (node (ref "U5") (pin "13.R") (pinfunction "13_13.R") (pintype "bidirectional"))
      (node (ref "U6") (pin "27") (pinfunction "PC4_27") (pintype "bidirectional"))
    )
    (net (code "55") (name "VDD") (class "Default")
      (node (ref "C1") (pin "1") (pinfunction "+_1") (pintype "passive"))
      (node (ref "C12") (pin "1") (pinfunction "+_1") (pintype "passive"))
      (node (ref "C13") (pin "1") (pinfunction "+_1") (pintype "passive"))
      (node (ref "C2") (pin "1") (pinfunction "+_1") (pintype "passive"))
      (node (ref "C3") (pin "1") (pinfunction "+_1") (pintype "passive"))
      (node (ref "C6") (pin "1") (pinfunction "+_1") (pintype "passive"))
      (node (ref "J1") (pin "2") (pinfunction "2_2") (pintype "bidirectional"))
      (node (ref "J4") (pin "2") (pinfunction "2.VDD(PWR)_2") (pintype "bidirectional"))
      (node (ref "J5") (pin "2") (pinfunction "2.VDD_2") (pintype "bidirectional"))
      (node (ref "J6") (pin "2") (pinfunction "2_2") (pintype "bidirectional"))
      (node (ref "J8") (pin "2") (pinfunction "2.VDD_2") (pintype "bidirectional"))
      (node (ref "J9") (pin "2") (pinfunction "2.VDD_2") (pintype "bidirectional"))
      (node (ref "LED1") (pin "4") (pinfunction "3.+_4") (pintype "passive"))
      (node (ref "R10") (pin "1") (pinfunction "1_1") (pintype "passive"))
      (node (ref "R11") (pin "1") (pinfunction "1_1") (pintype "passive"))
      (node (ref "R15") (pin "1") (pinfunction "1_1") (pintype "passive"))
      (node (ref "R16") (pin "1") (pinfunction "1_1") (pintype "passive"))
      (node (ref "R4") (pin "1") (pinfunction "1_1") (pintype "passive"))
      (node (ref "R5") (pin "1") (pinfunction "1_1") (pintype "passive"))
      (node (ref "R6") (pin "1") (pinfunction "1_1") (pintype "passive"))
      (node (ref "R8") (pin "1") (pinfunction "1_1") (pintype "passive"))
      (node (ref "U$3") (pin "2.VDD") (pinfunction "1.VDD_2.VDD") (pintype "bidirectional"))
      (node (ref "U3") (pin "1") (pinfunction "1.VDD_1") (pintype "bidirectional"))
      (node (ref "U4") (pin "2") (pinfunction "2.VDD_2") (pintype "bidirectional"))
      (node (ref "U5") (pin "1.L") (pinfunction "1_1.L") (pintype "bidirectional"))
      (node (ref "U5") (pin "1.R") (pinfunction "1_1.R") (pintype "bidirectional"))
      (node (ref "U6") (pin "4") (pinfunction "VCC_2_4") (pintype "power_in"))
      (node (ref "U6") (pin "6") (pinfunction "VCC_6") (pintype "power_in"))
    )
    (net (code "56") (name "XTAL1") (class "Default")
      (node (ref "C7") (pin "2") (pinfunction "+_2") (pintype "passive"))
      (node (ref "U6") (pin "7") (pinfunction "PB6_7") (pintype "bidirectional"))
      (node (ref "XTAL1") (pin "2") (pinfunction "2_2") (pintype "bidirectional"))
      (node (ref "XTAL1") (pin "4") (pinfunction "2_4") (pintype "bidirectional"))
    )
    (net (code "57") (name "XTAL2") (class "Default")
      (node (ref "C8") (pin "2") (pinfunction "+_2") (pintype "passive"))
      (node (ref "U6") (pin "8") (pinfunction "PB7_8") (pintype "bidirectional"))
      (node (ref "XTAL1") (pin "1") (pinfunction "1_1") (pintype "bidirectional"))
      (node (ref "XTAL1") (pin "3") (pinfunction "1_3") (pintype "bidirectional"))
    )
    (net (code "58") (name "unconnected-(J4-6.PGM-Pad6)") (class "Default")
      (node (ref "J4") (pin "6") (pinfunction "6.PGM_6") (pintype "bidirectional"))
    )
    (net (code "59") (name "unconnected-(J7-PadRING_SW)") (class "Default")
      (node (ref "J7") (pin "RING_SW") (pinfunction "RING_SW_RING_SW") (pintype "bidirectional"))
    )
    (net (code "60") (name "unconnected-(J8-5.ADC2-Pad5)") (class "Default")
      (node (ref "J8") (pin "5") (pinfunction "5.ADC2_5") (pintype "bidirectional"))
    )
    (net (code "61") (name "unconnected-(U2-(1)3V3-Pad1.3V3)") (class "Default")
      (node (ref "U2") (pin "1.3V3") (pinfunction "(1)3V3_1.3V3") (pintype "bidirectional"))
    )
    (net (code "62") (name "unconnected-(U2-(2)DTR-Pad2.DTR)") (class "Default")
      (node (ref "U2") (pin "2.DTR") (pinfunction "(2)DTR_2.DTR") (pintype "bidirectional"))
    )
    (net (code "63") (name "unconnected-(U7-(1)3V3-Pad1.3V3)") (class "Default")
      (node (ref "U7") (pin "1.3V3") (pinfunction "(1)3V3_1.3V3") (pintype "bidirectional"))
    )
  )
)
